# 4_-MCU_POWER.net
KiCad netlist of a schematic drawn in Altium Designer
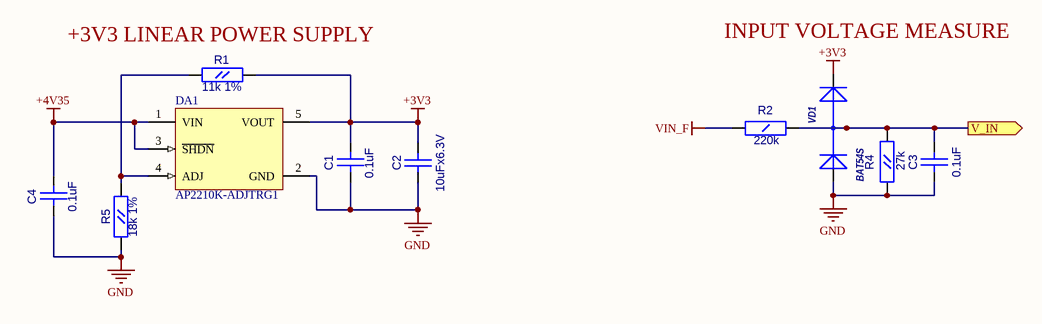
[diagram p0: [4]-MCU_POWER.SchDoc]

(export (version "E")
  (design (tool "Eeschema 10.0.6"))
  (components
    (comp (ref "C1")
      (value "0.1uF")
      (footprint "CC0603")
      (description "CC0603")
      (libsource (lib "gprs_modem_2") (part "CC0603"))
    )
    (comp (ref "C2")
      (value "10uFx6.3V")
      (footprint "CC0805")
      (description "CC0805")
      (libsource (lib "gprs_modem_2") (part "CC0805"))
    )
    (comp (ref "C3")
      (value "0.1uF")
      (footprint "CC0603")
      (description "CC0603")
      (libsource (lib "gprs_modem_2") (part "CC0603"))
    )
    (comp (ref "C4")
      (value "0.1uF")
      (footprint "CC0603")
      (description "CC0603")
      (libsource (lib "gprs_modem_2") (part "CC0603"))
    )
    (comp (ref "DA1")
      (value "AP2210K-ADJTRG1")
      (footprint "SOT23-5")
      (fields (field (name "PUBLISHER") "Altium Limited"))
      (libsource (lib "gprs_modem_2") (part "MCP1824T-ADJE/OT"))
    )
    (comp (ref "R1")
      (value "11k 1%")
      (footprint "RC0603")
      (description "RC0603")
      (libsource (lib "gprs_modem_2") (part "RC0603"))
    )
    (comp (ref "R2")
      (value "220k")
      (footprint "RC1206")
      (description "RC1206")
      (libsource (lib "fizik_lib") (part "RC1206"))
    )
    (comp (ref "R4")
      (value "27k")
      (footprint "RC0603")
      (description "RC0603")
      (libsource (lib "gprs_modem_2") (part "RC0603"))
    )
    (comp (ref "R5")
      (value "18k 1%")
      (footprint "RC0603")
      (description "RC0603")
      (libsource (lib "gprs_modem_2") (part "RC0603"))
    )
    (comp (ref "VD1")
      (value "BAT54S")
      (footprint "SOT-23(GSD)")
      (description "1.0 Ampere General Purpose Rectifier")
      (libsource (lib "gprs_modem_2") (part "BAT54S"))
    )
  )
  (nets
    (net (code "1") (name "+3V3") (class "Default")
      (node (ref "C1") (pin "1") (pinfunction "A_1") (pintype "passive"))
      (node (ref "C2") (pin "2") (pinfunction "B_2") (pintype "passive"))
      (node (ref "DA1") (pin "5") (pinfunction "VOUT_5") (pintype "power_in"))
      (node (ref "R1") (pin "2") (pinfunction "B_2") (pintype "passive"))
      (node (ref "VD1") (pin "2") (pinfunction "K_2") (pintype "passive"))
    )
    (net (code "2") (name "+4V35") (class "Default")
      (node (ref "C4") (pin "1") (pinfunction "A_1") (pintype "passive"))
      (node (ref "DA1") (pin "1") (pinfunction "VIN_1") (pintype "power_in"))
      (node (ref "DA1") (pin "3") (pinfunction "~{SHDN}_3") (pintype "input"))
    )
    (net (code "3") (name "/V_IN") (class "Default")
      (node (ref "C3") (pin "2") (pinfunction "B_2") (pintype "passive"))
      (node (ref "R2") (pin "2") (pinfunction "B_2") (pintype "passive"))
      (node (ref "R4") (pin "2") (pinfunction "B_2") (pintype "passive"))
      (node (ref "VD1") (pin "3") (pinfunction "AK_3") (pintype "passive"))
    )
    (net (code "4") (name "GND") (class "Default")
      (node (ref "C1") (pin "2") (pinfunction "B_2") (pintype "passive"))
      (node (ref "C2") (pin "1") (pinfunction "A_1") (pintype "passive"))
      (node (ref "C3") (pin "1") (pinfunction "A_1") (pintype "passive"))
      (node (ref "C4") (pin "2") (pinfunction "B_2") (pintype "passive"))
      (node (ref "DA1") (pin "2") (pinfunction "GND_2") (pintype "power_in"))
      (node (ref "R4") (pin "1") (pinfunction "A_1") (pintype "passive"))
      (node (ref "R5") (pin "1") (pinfunction "A_1") (pintype "passive"))
      (node (ref "VD1") (pin "1") (pinfunction "A_1") (pintype "passive"))
    )
    (net (code "5") (name "Net-(DA1-ADJ)") (class "Default")
      (node (ref "DA1") (pin "4") (pinfunction "ADJ_4") (pintype "input"))
      (node (ref "R1") (pin "1") (pinfunction "A_1") (pintype "passive"))
      (node (ref "R5") (pin "2") (pinfunction "B_2") (pintype "passive"))
    )
    (net (code "6") (name "VIN_F") (class "Default")
      (node (ref "R2") (pin "1") (pinfunction "A_1") (pintype "passive"))
    )
  )
)
